# capstoneIO.net
KiCad netlist of a schematic drawn in EAGLE
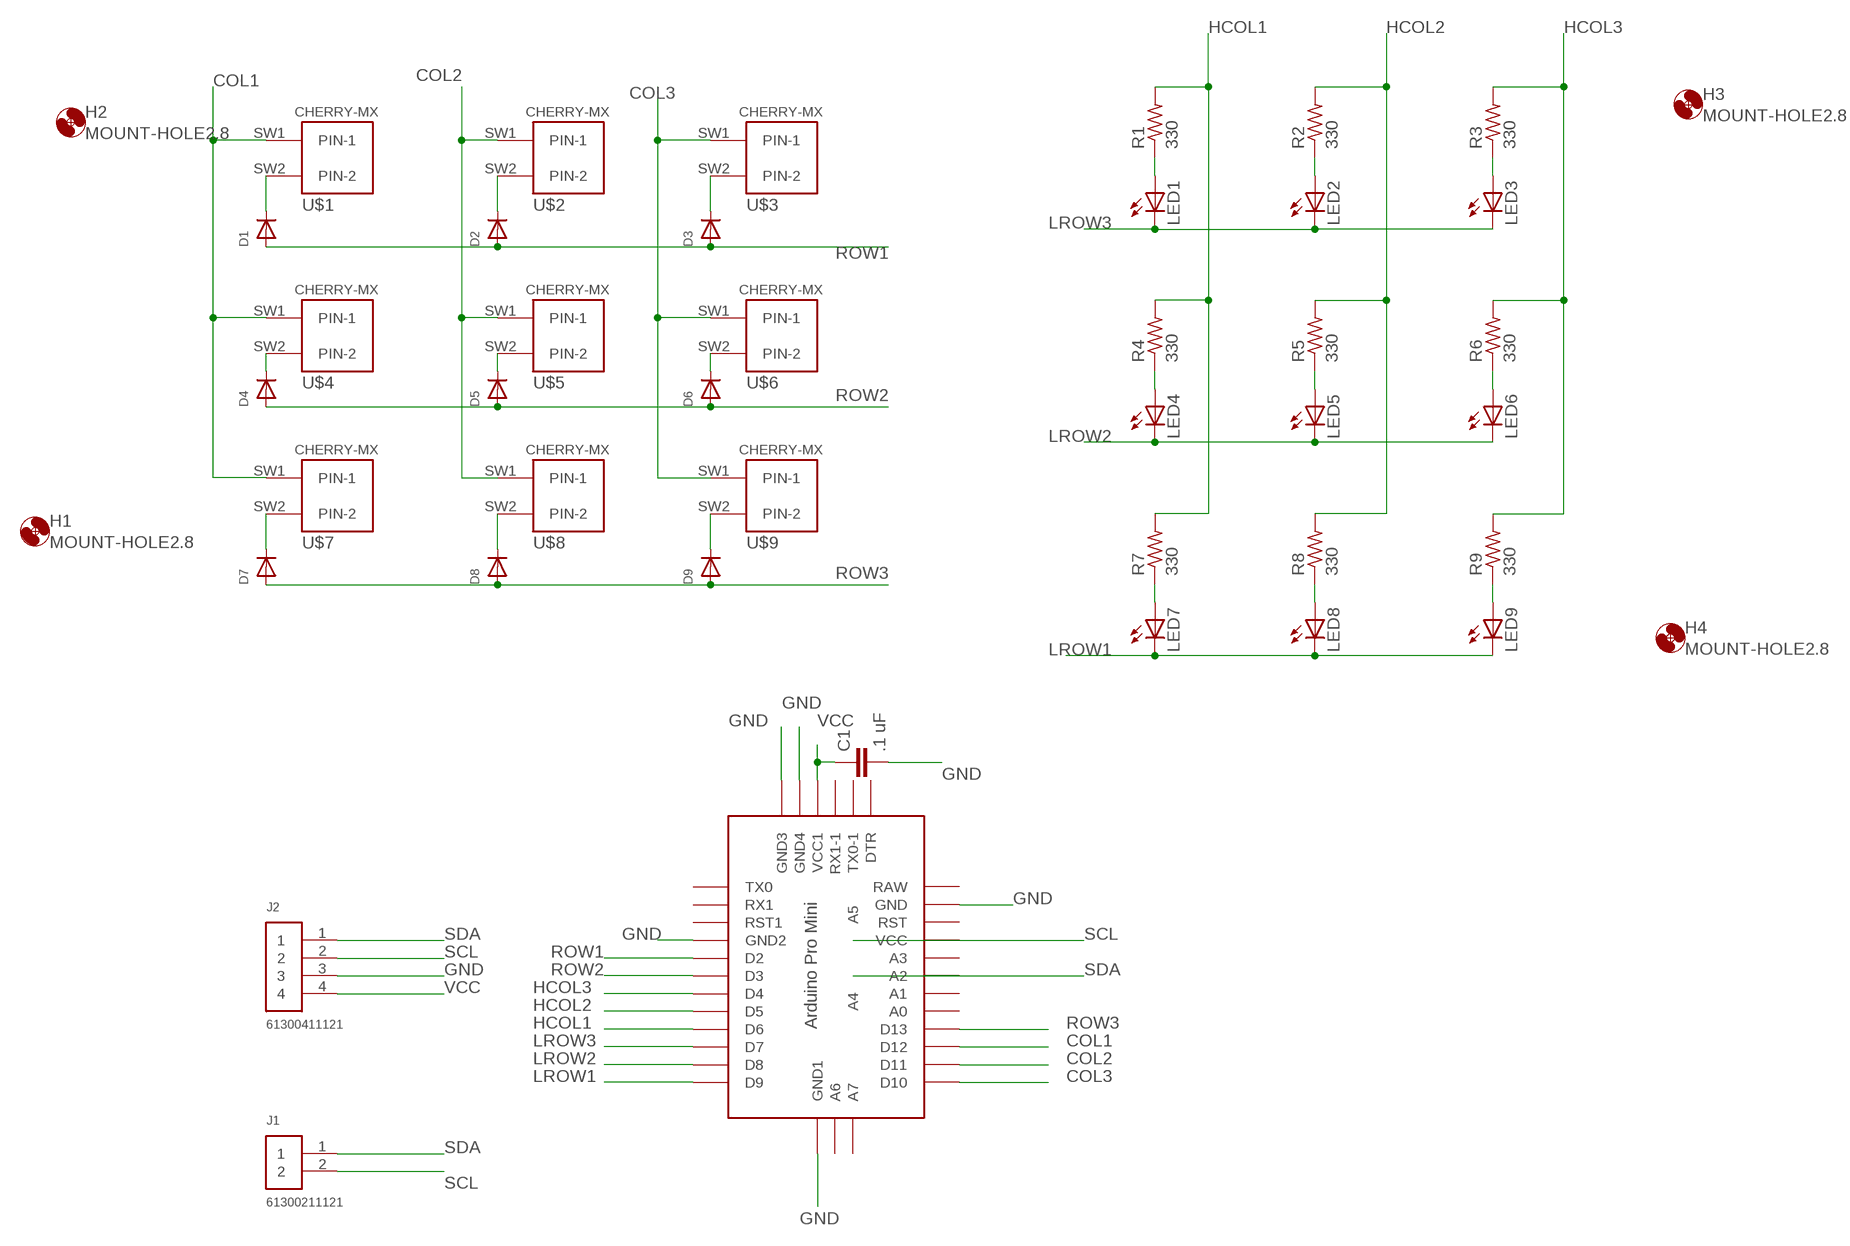
[diagram p0: schematic, sheet 1]

(export (version "E")
  (design (tool "Eeschema 10.0.6"))
  (components
    (comp (ref "C1")
      (value ".1 uF")
      (footprint "eagle-import:C075-032X103-AARON")
      (libsource (lib "eagle-import") (part "C-EU075-032X103-AARON"))
    )
    (comp (ref "D1")
      (value "DIODEDO-1N4148")
      (footprint "eagle-import:DO-1N4148")
      (libsource (lib "eagle-import") (part "DIODEDO-1N4148"))
    )
    (comp (ref "D2")
      (value "DIODEDO-1N4148")
      (footprint "eagle-import:DO-1N4148")
      (libsource (lib "eagle-import") (part "DIODEDO-1N4148"))
    )
    (comp (ref "D3")
      (value "DIODEDO-1N4148")
      (footprint "eagle-import:DO-1N4148")
      (libsource (lib "eagle-import") (part "DIODEDO-1N4148"))
    )
    (comp (ref "D4")
      (value "DIODEDO-1N4148")
      (footprint "eagle-import:DO-1N4148")
      (libsource (lib "eagle-import") (part "DIODEDO-1N4148"))
    )
    (comp (ref "D5")
      (value "DIODEDO-1N4148")
      (footprint "eagle-import:DO-1N4148")
      (libsource (lib "eagle-import") (part "DIODEDO-1N4148"))
    )
    (comp (ref "D6")
      (value "DIODEDO-1N4148")
      (footprint "eagle-import:DO-1N4148")
      (libsource (lib "eagle-import") (part "DIODEDO-1N4148"))
    )
    (comp (ref "D7")
      (value "DIODEDO-1N4148")
      (footprint "eagle-import:DO-1N4148")
      (libsource (lib "eagle-import") (part "DIODEDO-1N4148"))
    )
    (comp (ref "D8")
      (value "DIODEDO-1N4148")
      (footprint "eagle-import:DO-1N4148")
      (libsource (lib "eagle-import") (part "DIODEDO-1N4148"))
    )
    (comp (ref "D9")
      (value "DIODEDO-1N4148")
      (footprint "eagle-import:DO-1N4148")
      (libsource (lib "eagle-import") (part "DIODEDO-1N4148"))
    )
    (comp (ref "H1")
      (value "MOUNT-HOLE2.8")
      (footprint "eagle-import:2,8")
      (libsource (lib "eagle-import") (part "MOUNT-HOLE2.8"))
    )
    (comp (ref "H2")
      (value "MOUNT-HOLE2.8")
      (footprint "eagle-import:2,8")
      (libsource (lib "eagle-import") (part "MOUNT-HOLE2.8"))
    )
    (comp (ref "H3")
      (value "MOUNT-HOLE2.8")
      (footprint "eagle-import:2,8")
      (libsource (lib "eagle-import") (part "MOUNT-HOLE2.8"))
    )
    (comp (ref "H4")
      (value "MOUNT-HOLE2.8")
      (footprint "eagle-import:2,8")
      (libsource (lib "eagle-import") (part "MOUNT-HOLE2.8"))
    )
    (comp (ref "J1")
      (value "61300211121")
      (footprint "eagle-import:61300211121")
      (fields
        (field (name "DIGI_KEY_PART_NUMBER") "732-5315-ND")
        (field (name "MANUFACTURER") "Wurth Electronics Inc.")
        (field (name "CREATED_BY") "PCBLayout.com")
      )
      (libsource (lib "eagle-import") (part "61300211121"))
    )
    (comp (ref "J2")
      (value "61300411121")
      (footprint "eagle-import:61300411121")
      (fields
        (field (name "DIGI_KEY_PART_NUMBER") "732-5317-ND")
        (field (name "MANUFACTURER") "Wurth Electronics Inc.")
        (field (name "CREATED_BY") "PCBLayout.com")
      )
      (libsource (lib "eagle-import") (part "61300411121"))
    )
    (comp (ref "LED1")
      (value "LED5MM")
      (footprint "eagle-import:LED5MM")
      (libsource (lib "eagle-import") (part "LED5MM"))
    )
    (comp (ref "LED2")
      (value "LED5MM")
      (footprint "eagle-import:LED5MM")
      (libsource (lib "eagle-import") (part "LED5MM"))
    )
    (comp (ref "LED3")
      (value "LED5MM")
      (footprint "eagle-import:LED5MM")
      (libsource (lib "eagle-import") (part "LED5MM"))
    )
    (comp (ref "LED4")
      (value "LED5MM")
      (footprint "eagle-import:LED5MM")
      (libsource (lib "eagle-import") (part "LED5MM"))
    )
    (comp (ref "LED5")
      (value "LED5MM")
      (footprint "eagle-import:LED5MM")
      (libsource (lib "eagle-import") (part "LED5MM"))
    )
    (comp (ref "LED6")
      (value "LED5MM")
      (footprint "eagle-import:LED5MM")
      (libsource (lib "eagle-import") (part "LED5MM"))
    )
    (comp (ref "LED7")
      (value "LED5MM")
      (footprint "eagle-import:LED5MM")
      (libsource (lib "eagle-import") (part "LED5MM"))
    )
    (comp (ref "LED8")
      (value "LED5MM")
      (footprint "eagle-import:LED5MM")
      (libsource (lib "eagle-import") (part "LED5MM"))
    )
    (comp (ref "LED9")
      (value "LED5MM")
      (footprint "eagle-import:LED5MM")
      (libsource (lib "eagle-import") (part "LED5MM"))
    )
    (comp (ref "R1")
      (value "330")
      (footprint "eagle-import:0204_7")
      (libsource (lib "eagle-import") (part "R-US_0204/7"))
    )
    (comp (ref "R2")
      (value "330")
      (footprint "eagle-import:0204_7")
      (libsource (lib "eagle-import") (part "R-US_0204/7"))
    )
    (comp (ref "R3")
      (value "330")
      (footprint "eagle-import:0204_7")
      (libsource (lib "eagle-import") (part "R-US_0204/7"))
    )
    (comp (ref "R4")
      (value "330")
      (footprint "eagle-import:0204_7")
      (libsource (lib "eagle-import") (part "R-US_0204/7"))
    )
    (comp (ref "R5")
      (value "330")
      (footprint "eagle-import:0204_7")
      (libsource (lib "eagle-import") (part "R-US_0204/7"))
    )
    (comp (ref "R6")
      (value "330")
      (footprint "eagle-import:0204_7")
      (libsource (lib "eagle-import") (part "R-US_0204/7"))
    )
    (comp (ref "R7")
      (value "330")
      (footprint "eagle-import:0204_7")
      (libsource (lib "eagle-import") (part "R-US_0204/7"))
    )
    (comp (ref "R8")
      (value "330")
      (footprint "eagle-import:0204_7")
      (libsource (lib "eagle-import") (part "R-US_0204/7"))
    )
    (comp (ref "R9")
      (value "330")
      (footprint "eagle-import:0204_7")
      (libsource (lib "eagle-import") (part "R-US_0204/7"))
    )
    (comp (ref "U$1")
      (value "CHERRY-MX")
      (footprint "eagle-import:CHERRY-MX")
      (libsource (lib "eagle-import") (part "CHERRY-MX"))
    )
    (comp (ref "U$2")
      (value "CHERRY-MX")
      (footprint "eagle-import:CHERRY-MX")
      (libsource (lib "eagle-import") (part "CHERRY-MX"))
    )
    (comp (ref "U$3")
      (value "CHERRY-MX")
      (footprint "eagle-import:CHERRY-MX")
      (libsource (lib "eagle-import") (part "CHERRY-MX"))
    )
    (comp (ref "U$4")
      (value "CHERRY-MX")
      (footprint "eagle-import:CHERRY-MX")
      (libsource (lib "eagle-import") (part "CHERRY-MX"))
    )
    (comp (ref "U$5")
      (value "CHERRY-MX")
      (footprint "eagle-import:CHERRY-MX")
      (libsource (lib "eagle-import") (part "CHERRY-MX"))
    )
    (comp (ref "U$6")
      (value "CHERRY-MX")
      (footprint "eagle-import:CHERRY-MX")
      (libsource (lib "eagle-import") (part "CHERRY-MX"))
    )
    (comp (ref "U$7")
      (value "CHERRY-MX")
      (footprint "eagle-import:CHERRY-MX")
      (libsource (lib "eagle-import") (part "CHERRY-MX"))
    )
    (comp (ref "U$8")
      (value "CHERRY-MX")
      (footprint "eagle-import:CHERRY-MX")
      (libsource (lib "eagle-import") (part "CHERRY-MX"))
    )
    (comp (ref "U$9")
      (value "CHERRY-MX")
      (footprint "eagle-import:CHERRY-MX")
      (libsource (lib "eagle-import") (part "CHERRY-MX"))
    )
    (comp (ref "U$10")
      (value "ABK-PRO-MINI")
      (footprint "eagle-import:ABK-PRO-MINI")
      (libsource (lib "eagle-import") (part "ABK-PRO-MINI"))
    )
  )
  (nets
    (net (code "1") (name "/COL1") (class "Default")
      (node (ref "U$1") (pin "SW1") (pinfunction "PIN-1_SW1") (pintype "bidirectional"))
      (node (ref "U$10") (pin "D12") (pinfunction "D12_D12") (pintype "bidirectional"))
      (node (ref "U$4") (pin "SW1") (pinfunction "PIN-1_SW1") (pintype "bidirectional"))
      (node (ref "U$7") (pin "SW1") (pinfunction "PIN-1_SW1") (pintype "bidirectional"))
    )
    (net (code "2") (name "/COL2") (class "Default")
      (node (ref "U$10") (pin "D11") (pinfunction "D11_D11") (pintype "bidirectional"))
      (node (ref "U$2") (pin "SW1") (pinfunction "PIN-1_SW1") (pintype "bidirectional"))
      (node (ref "U$5") (pin "SW1") (pinfunction "PIN-1_SW1") (pintype "bidirectional"))
      (node (ref "U$8") (pin "SW1") (pinfunction "PIN-1_SW1") (pintype "bidirectional"))
    )
    (net (code "3") (name "/COL3") (class "Default")
      (node (ref "U$10") (pin "D10") (pinfunction "D10_D10") (pintype "bidirectional"))
      (node (ref "U$3") (pin "SW1") (pinfunction "PIN-1_SW1") (pintype "bidirectional"))
      (node (ref "U$6") (pin "SW1") (pinfunction "PIN-1_SW1") (pintype "bidirectional"))
      (node (ref "U$9") (pin "SW1") (pinfunction "PIN-1_SW1") (pintype "bidirectional"))
    )
    (net (code "4") (name "/GND") (class "Default")
      (node (ref "C1") (pin "2") (pinfunction "2_2") (pintype "passive"))
      (node (ref "J2") (pin "3") (pinfunction "3_3") (pintype "passive"))
      (node (ref "U$10") (pin "GND") (pinfunction "GND_GND") (pintype "bidirectional"))
      (node (ref "U$10") (pin "GND1") (pinfunction "GND2_GND1") (pintype "bidirectional"))
      (node (ref "U$10") (pin "GND2") (pinfunction "GND3_GND2") (pintype "bidirectional"))
      (node (ref "U$10") (pin "GND3") (pinfunction "GND4_GND3") (pintype "bidirectional"))
      (node (ref "U$10") (pin "GND4") (pinfunction "GND1_GND4") (pintype "bidirectional"))
    )
    (net (code "5") (name "/HCOL1") (class "Default")
      (node (ref "R1") (pin "2") (pinfunction "2_2") (pintype "passive"))
      (node (ref "R4") (pin "2") (pinfunction "2_2") (pintype "passive"))
      (node (ref "R7") (pin "2") (pinfunction "2_2") (pintype "passive"))
      (node (ref "U$10") (pin "D6") (pinfunction "D6_D6") (pintype "bidirectional"))
    )
    (net (code "6") (name "/HCOL2") (class "Default")
      (node (ref "R2") (pin "2") (pinfunction "2_2") (pintype "passive"))
      (node (ref "R5") (pin "2") (pinfunction "2_2") (pintype "passive"))
      (node (ref "R8") (pin "2") (pinfunction "2_2") (pintype "passive"))
      (node (ref "U$10") (pin "D5") (pinfunction "D5_D5") (pintype "bidirectional"))
    )
    (net (code "7") (name "/HCOL3") (class "Default")
      (node (ref "R3") (pin "2") (pinfunction "2_2") (pintype "passive"))
      (node (ref "R6") (pin "2") (pinfunction "2_2") (pintype "passive"))
      (node (ref "R9") (pin "2") (pinfunction "2_2") (pintype "passive"))
      (node (ref "U$10") (pin "D4") (pinfunction "D4_D4") (pintype "bidirectional"))
    )
    (net (code "8") (name "/LROW1") (class "Default")
      (node (ref "LED7") (pin "K") (pinfunction "C_K") (pintype "passive"))
      (node (ref "LED8") (pin "K") (pinfunction "C_K") (pintype "passive"))
      (node (ref "LED9") (pin "K") (pinfunction "C_K") (pintype "passive"))
      (node (ref "U$10") (pin "D9") (pinfunction "D9_D9") (pintype "bidirectional"))
    )
    (net (code "9") (name "/LROW2") (class "Default")
      (node (ref "LED4") (pin "K") (pinfunction "C_K") (pintype "passive"))
      (node (ref "LED5") (pin "K") (pinfunction "C_K") (pintype "passive"))
      (node (ref "LED6") (pin "K") (pinfunction "C_K") (pintype "passive"))
      (node (ref "U$10") (pin "D8") (pinfunction "D8_D8") (pintype "bidirectional"))
    )
    (net (code "10") (name "/LROW3") (class "Default")
      (node (ref "LED1") (pin "K") (pinfunction "C_K") (pintype "passive"))
      (node (ref "LED2") (pin "K") (pinfunction "C_K") (pintype "passive"))
      (node (ref "LED3") (pin "K") (pinfunction "C_K") (pintype "passive"))
      (node (ref "U$10") (pin "D7") (pinfunction "D7_D7") (pintype "bidirectional"))
    )
    (net (code "11") (name "/ROW1") (class "Default")
      (node (ref "D1") (pin "A") (pinfunction "A_A") (pintype "passive"))
      (node (ref "D2") (pin "A") (pinfunction "A_A") (pintype "passive"))
      (node (ref "D3") (pin "A") (pinfunction "A_A") (pintype "passive"))
      (node (ref "U$10") (pin "D2") (pinfunction "D2_D2") (pintype "bidirectional"))
    )
    (net (code "12") (name "/ROW2") (class "Default")
      (node (ref "D4") (pin "A") (pinfunction "A_A") (pintype "passive"))
      (node (ref "D5") (pin "A") (pinfunction "A_A") (pintype "passive"))
      (node (ref "D6") (pin "A") (pinfunction "A_A") (pintype "passive"))
      (node (ref "U$10") (pin "D3") (pinfunction "D3_D3") (pintype "bidirectional"))
    )
    (net (code "13") (name "/ROW3") (class "Default")
      (node (ref "D7") (pin "A") (pinfunction "A_A") (pintype "passive"))
      (node (ref "D8") (pin "A") (pinfunction "A_A") (pintype "passive"))
      (node (ref "D9") (pin "A") (pinfunction "A_A") (pintype "passive"))
      (node (ref "U$10") (pin "D13") (pinfunction "D13_D13") (pintype "bidirectional"))
    )
    (net (code "14") (name "/SCL") (class "Default")
      (node (ref "J1") (pin "2") (pinfunction "2_2") (pintype "passive"))
      (node (ref "J2") (pin "2") (pinfunction "2_2") (pintype "passive"))
      (node (ref "U$10") (pin "A5") (pinfunction "A5_A5") (pintype "bidirectional"))
    )
    (net (code "15") (name "/SDA") (class "Default")
      (node (ref "J1") (pin "1") (pinfunction "1_1") (pintype "passive"))
      (node (ref "J2") (pin "1") (pinfunction "1_1") (pintype "passive"))
      (node (ref "U$10") (pin "A4") (pinfunction "A4_A4") (pintype "bidirectional"))
    )
    (net (code "16") (name "/VCC") (class "Default")
      (node (ref "C1") (pin "1") (pinfunction "1_1") (pintype "passive"))
      (node (ref "J2") (pin "4") (pinfunction "4_4") (pintype "passive"))
      (node (ref "U$10") (pin "VCC1") (pinfunction "VCC1_VCC1") (pintype "bidirectional"))
    )
    (net (code "17") (name "Net-(LED1-PadA)") (class "Default")
      (node (ref "LED1") (pin "A") (pinfunction "A_A") (pintype "passive"))
      (node (ref "R1") (pin "1") (pinfunction "1_1") (pintype "passive"))
    )
    (net (code "18") (name "Net-(LED2-PadA)") (class "Default")
      (node (ref "LED2") (pin "A") (pinfunction "A_A") (pintype "passive"))
      (node (ref "R2") (pin "1") (pinfunction "1_1") (pintype "passive"))
    )
    (net (code "19") (name "Net-(LED3-PadA)") (class "Default")
      (node (ref "LED3") (pin "A") (pinfunction "A_A") (pintype "passive"))
      (node (ref "R3") (pin "1") (pinfunction "1_1") (pintype "passive"))
    )
    (net (code "20") (name "Net-(LED4-PadA)") (class "Default")
      (node (ref "LED4") (pin "A") (pinfunction "A_A") (pintype "passive"))
      (node (ref "R4") (pin "1") (pinfunction "1_1") (pintype "passive"))
    )
    (net (code "21") (name "Net-(LED5-PadA)") (class "Default")
      (node (ref "LED5") (pin "A") (pinfunction "A_A") (pintype "passive"))
      (node (ref "R5") (pin "1") (pinfunction "1_1") (pintype "passive"))
    )
    (net (code "22") (name "Net-(LED6-PadA)") (class "Default")
      (node (ref "LED6") (pin "A") (pinfunction "A_A") (pintype "passive"))
      (node (ref "R6") (pin "1") (pinfunction "1_1") (pintype "passive"))
    )
    (net (code "23") (name "Net-(LED7-PadA)") (class "Default")
      (node (ref "LED7") (pin "A") (pinfunction "A_A") (pintype "passive"))
      (node (ref "R7") (pin "1") (pinfunction "1_1") (pintype "passive"))
    )
    (net (code "24") (name "Net-(LED8-PadA)") (class "Default")
      (node (ref "LED8") (pin "A") (pinfunction "A_A") (pintype "passive"))
      (node (ref "R8") (pin "1") (pinfunction "1_1") (pintype "passive"))
    )
    (net (code "25") (name "Net-(LED9-PadA)") (class "Default")
      (node (ref "LED9") (pin "A") (pinfunction "A_A") (pintype "passive"))
      (node (ref "R9") (pin "1") (pinfunction "1_1") (pintype "passive"))
    )
    (net (code "26") (name "Net-(U$1-PIN-2)") (class "Default")
      (node (ref "D1") (pin "C") (pinfunction "C_C") (pintype "passive"))
      (node (ref "U$1") (pin "SW2") (pinfunction "PIN-2_SW2") (pintype "bidirectional"))
    )
    (net (code "27") (name "Net-(U$2-PIN-2)") (class "Default")
      (node (ref "D2") (pin "C") (pinfunction "C_C") (pintype "passive"))
      (node (ref "U$2") (pin "SW2") (pinfunction "PIN-2_SW2") (pintype "bidirectional"))
    )
    (net (code "28") (name "Net-(U$3-PIN-2)") (class "Default")
      (node (ref "D3") (pin "C") (pinfunction "C_C") (pintype "passive"))
      (node (ref "U$3") (pin "SW2") (pinfunction "PIN-2_SW2") (pintype "bidirectional"))
    )
    (net (code "29") (name "Net-(U$4-PIN-2)") (class "Default")
      (node (ref "D4") (pin "C") (pinfunction "C_C") (pintype "passive"))
      (node (ref "U$4") (pin "SW2") (pinfunction "PIN-2_SW2") (pintype "bidirectional"))
    )
    (net (code "30") (name "Net-(U$5-PIN-2)") (class "Default")
      (node (ref "D5") (pin "C") (pinfunction "C_C") (pintype "passive"))
      (node (ref "U$5") (pin "SW2") (pinfunction "PIN-2_SW2") (pintype "bidirectional"))
    )
    (net (code "31") (name "Net-(U$6-PIN-2)") (class "Default")
      (node (ref "D6") (pin "C") (pinfunction "C_C") (pintype "passive"))
      (node (ref "U$6") (pin "SW2") (pinfunction "PIN-2_SW2") (pintype "bidirectional"))
    )
    (net (code "32") (name "Net-(U$7-PIN-2)") (class "Default")
      (node (ref "D7") (pin "C") (pinfunction "C_C") (pintype "passive"))
      (node (ref "U$7") (pin "SW2") (pinfunction "PIN-2_SW2") (pintype "bidirectional"))
    )
    (net (code "33") (name "Net-(U$8-PIN-2)") (class "Default")
      (node (ref "D8") (pin "C") (pinfunction "C_C") (pintype "passive"))
      (node (ref "U$8") (pin "SW2") (pinfunction "PIN-2_SW2") (pintype "bidirectional"))
    )
    (net (code "34") (name "Net-(U$9-PIN-2)") (class "Default")
      (node (ref "D9") (pin "C") (pinfunction "C_C") (pintype "passive"))
      (node (ref "U$9") (pin "SW2") (pinfunction "PIN-2_SW2") (pintype "bidirectional"))
    )
    (net (code "35") (name "unconnected-(U$10-PadA0)") (class "Default")
      (node (ref "U$10") (pin "A0") (pinfunction "A0_A0") (pintype "bidirectional"))
    )
    (net (code "36") (name "unconnected-(U$10-PadA1)") (class "Default")
      (node (ref "U$10") (pin "A1") (pinfunction "A1_A1") (pintype "bidirectional"))
    )
    (net (code "37") (name "unconnected-(U$10-PadA2)") (class "Default")
      (node (ref "U$10") (pin "A2") (pinfunction "A2_A2") (pintype "bidirectional"))
    )
    (net (code "38") (name "unconnected-(U$10-PadA3)") (class "Default")
      (node (ref "U$10") (pin "A3") (pinfunction "A3_A3") (pintype "bidirectional"))
    )
    (net (code "39") (name "unconnected-(U$10-PadA6)") (class "Default")
      (node (ref "U$10") (pin "A6") (pinfunction "A6_A6") (pintype "bidirectional"))
    )
    (net (code "40") (name "unconnected-(U$10-PadA7)") (class "Default")
      (node (ref "U$10") (pin "A7") (pinfunction "A7_A7") (pintype "bidirectional"))
    )
    (net (code "41") (name "unconnected-(U$10-PadDTR)") (class "Default")
      (node (ref "U$10") (pin "DTR") (pinfunction "DTR_DTR") (pintype "bidirectional"))
    )
    (net (code "42") (name "unconnected-(U$10-PadRAW)") (class "Default")
      (node (ref "U$10") (pin "RAW") (pinfunction "RAW_RAW") (pintype "bidirectional"))
    )
    (net (code "43") (name "unconnected-(U$10-PadRST)") (class "Default")
      (node (ref "U$10") (pin "RST") (pinfunction "RST_RST") (pintype "bidirectional"))
    )
    (net (code "44") (name "unconnected-(U$10-PadRST1)") (class "Default")
      (node (ref "U$10") (pin "RST1") (pinfunction "RST1_RST1") (pintype "bidirectional"))
    )
    (net (code "45") (name "unconnected-(U$10-PadRX1)") (class "Default")
      (node (ref "U$10") (pin "RX1") (pinfunction "RX1_RX1") (pintype "bidirectional"))
    )
    (net (code "46") (name "unconnected-(U$10-PadRX1-1)") (class "Default")
      (node (ref "U$10") (pin "RX1-1") (pinfunction "RX1-1_RX1-1") (pintype "bidirectional"))
    )
    (net (code "47") (name "unconnected-(U$10-PadTX0)") (class "Default")
      (node (ref "U$10") (pin "TX0") (pinfunction "TX0_TX0") (pintype "bidirectional"))
    )
    (net (code "48") (name "unconnected-(U$10-PadTX0-1)") (class "Default")
      (node (ref "U$10") (pin "TX0-1") (pinfunction "TX0-1_TX0-1") (pintype "bidirectional"))
    )
    (net (code "49") (name "unconnected-(U$10-PadVCC)") (class "Default")
      (node (ref "U$10") (pin "VCC") (pinfunction "VCC_VCC") (pintype "bidirectional"))
    )
  )
)
